# HMC5883Shield.net
KiCad netlist of a schematic drawn in EAGLE
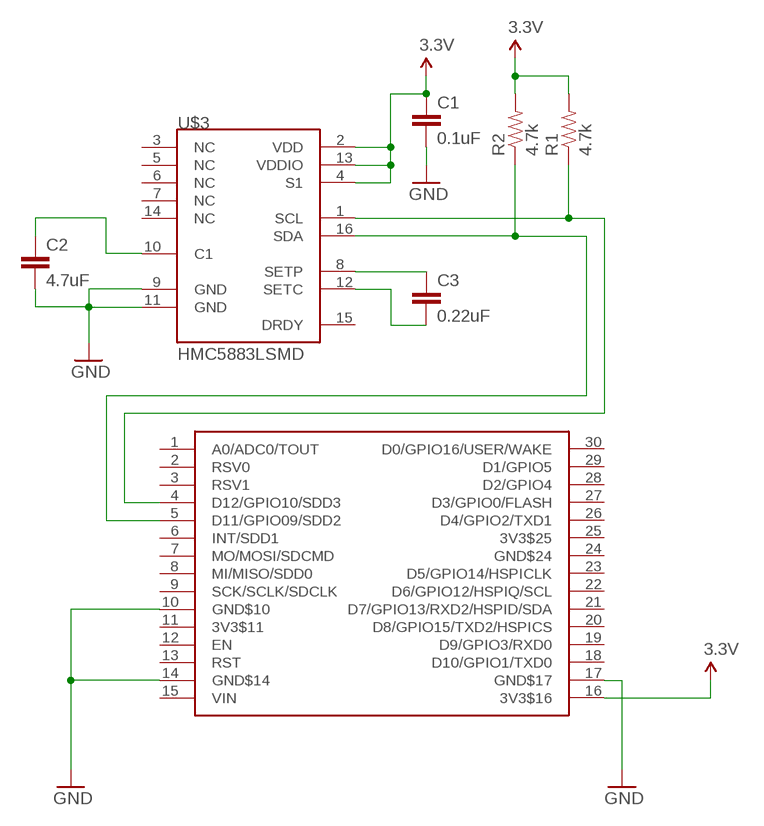
[diagram p0: schematic, sheet 1]

(export (version "E")
  (design (tool "Eeschema 10.0.6"))
  (components
    (comp (ref "C1")
      (value "0.1uF")
      (footprint "eagle-import:0402-CAP")
      (libsource (lib "eagle-import") (part "CAP0402-CAP"))
    )
    (comp (ref "C2")
      (value "4.7uF")
      (footprint "eagle-import:0402-CAP")
      (libsource (lib "eagle-import") (part "CAP0402-CAP"))
    )
    (comp (ref "C3")
      (value "0.22uF")
      (footprint "eagle-import:0402-CAP")
      (libsource (lib "eagle-import") (part "CAP0402-CAP"))
    )
    (comp (ref "R1")
      (value "4.7k")
      (footprint "eagle-import:0402-RES")
      (libsource (lib "eagle-import") (part "RESISTOR0402-RES"))
    )
    (comp (ref "R2")
      (value "4.7k")
      (footprint "eagle-import:0402-RES")
      (libsource (lib "eagle-import") (part "RESISTOR0402-RES"))
    )
    (comp (ref "U$1")
      (value "NERDSHIELD")
      (footprint "eagle-import:NERDUINO_STACK")
      (libsource (lib "eagle-import") (part "NERDSHIELD"))
    )
    (comp (ref "U$3")
      (value "HMC5883LSMD")
      (footprint "eagle-import:16LPCC")
      (libsource (lib "eagle-import") (part "HMC5883LSMD"))
    )
  )
  (nets
    (net (code "1") (name "3.3V") (class "Default")
      (node (ref "C1") (pin "1") (pinfunction "1_1") (pintype "passive"))
      (node (ref "R1") (pin "2") (pinfunction "2_2") (pintype "passive"))
      (node (ref "R2") (pin "2") (pinfunction "2_2") (pintype "passive"))
      (node (ref "U$1") (pin "16") (pinfunction "3V3$16_16") (pintype "bidirectional"))
      (node (ref "U$3") (pin "13") (pinfunction "VDDIO_13") (pintype "bidirectional"))
      (node (ref "U$3") (pin "2") (pinfunction "VDD_2") (pintype "bidirectional"))
      (node (ref "U$3") (pin "4") (pinfunction "S1_4") (pintype "bidirectional"))
    )
    (net (code "2") (name "GND") (class "Default")
      (node (ref "C1") (pin "2") (pinfunction "2_2") (pintype "passive"))
      (node (ref "C2") (pin "2") (pinfunction "2_2") (pintype "passive"))
      (node (ref "U$1") (pin "10") (pinfunction "GND$10_10") (pintype "bidirectional"))
      (node (ref "U$1") (pin "14") (pinfunction "GND$14_14") (pintype "bidirectional"))
      (node (ref "U$1") (pin "17") (pinfunction "GND$17_17") (pintype "bidirectional"))
      (node (ref "U$3") (pin "11") (pinfunction "GND_11") (pintype "bidirectional"))
      (node (ref "U$3") (pin "9") (pinfunction "GND_9") (pintype "bidirectional"))
    )
    (net (code "3") (name "Net-(U$1-D11{slash}GPIO09{slash}SDD2)") (class "Default")
      (node (ref "R2") (pin "1") (pinfunction "1_1") (pintype "passive"))
      (node (ref "U$1") (pin "5") (pinfunction "D11/GPIO09/SDD2_5") (pintype "bidirectional"))
      (node (ref "U$3") (pin "16") (pinfunction "SDA_16") (pintype "bidirectional"))
    )
    (net (code "4") (name "Net-(U$1-D12{slash}GPIO10{slash}SDD3)") (class "Default")
      (node (ref "R1") (pin "1") (pinfunction "1_1") (pintype "passive"))
      (node (ref "U$1") (pin "4") (pinfunction "D12/GPIO10/SDD3_4") (pintype "bidirectional"))
      (node (ref "U$3") (pin "1") (pinfunction "SCL_1") (pintype "bidirectional"))
    )
    (net (code "5") (name "Net-(U$3-C1)") (class "Default")
      (node (ref "C2") (pin "1") (pinfunction "1_1") (pintype "passive"))
      (node (ref "U$3") (pin "10") (pinfunction "C1_10") (pintype "bidirectional"))
    )
    (net (code "6") (name "Net-(U$3-SETC)") (class "Default")
      (node (ref "C3") (pin "2") (pinfunction "2_2") (pintype "passive"))
      (node (ref "U$3") (pin "12") (pinfunction "SETC_12") (pintype "bidirectional"))
    )
    (net (code "7") (name "Net-(U$3-SETP)") (class "Default")
      (node (ref "C3") (pin "1") (pinfunction "1_1") (pintype "passive"))
      (node (ref "U$3") (pin "8") (pinfunction "SETP_8") (pintype "bidirectional"))
    )
    (net (code "8") (name "unconnected-(U$1-3V3$11-Pad11)") (class "Default")
      (node (ref "U$1") (pin "11") (pinfunction "3V3$11_11") (pintype "bidirectional"))
    )
    (net (code "9") (name "unconnected-(U$1-3V3$25-Pad25)") (class "Default")
      (node (ref "U$1") (pin "25") (pinfunction "3V3$25_25") (pintype "bidirectional"))
    )
    (net (code "10") (name "unconnected-(U$1-A0{slash}ADC0{slash}TOUT-Pad1)") (class "Default")
      (node (ref "U$1") (pin "1") (pinfunction "A0/ADC0/TOUT_1") (pintype "bidirectional"))
    )
    (net (code "11") (name "unconnected-(U$1-D0{slash}GPIO16{slash}USER{slash}WAKE-Pad30)") (class "Default")
      (node (ref "U$1") (pin "30") (pinfunction "D0/GPIO16/USER/WAKE_30") (pintype "bidirectional"))
    )
    (net (code "12") (name "unconnected-(U$1-D1{slash}GPIO5-Pad29)") (class "Default")
      (node (ref "U$1") (pin "29") (pinfunction "D1/GPIO5_29") (pintype "bidirectional"))
    )
    (net (code "13") (name "unconnected-(U$1-D2{slash}GPIO4-Pad28)") (class "Default")
      (node (ref "U$1") (pin "28") (pinfunction "D2/GPIO4_28") (pintype "bidirectional"))
    )
    (net (code "14") (name "unconnected-(U$1-D3{slash}GPIO0{slash}FLASH-Pad27)") (class "Default")
      (node (ref "U$1") (pin "27") (pinfunction "D3/GPIO0/FLASH_27") (pintype "bidirectional"))
    )
    (net (code "15") (name "unconnected-(U$1-D4{slash}GPIO2{slash}TXD1-Pad26)") (class "Default")
      (node (ref "U$1") (pin "26") (pinfunction "D4/GPIO2/TXD1_26") (pintype "bidirectional"))
    )
    (net (code "16") (name "unconnected-(U$1-D5{slash}GPIO14{slash}HSPICLK-Pad23)") (class "Default")
      (node (ref "U$1") (pin "23") (pinfunction "D5/GPIO14/HSPICLK_23") (pintype "bidirectional"))
    )
    (net (code "17") (name "unconnected-(U$1-D6{slash}GPIO12{slash}HSPIQ{slash}SCL-Pad22)") (class "Default")
      (node (ref "U$1") (pin "22") (pinfunction "D6/GPIO12/HSPIQ/SCL_22") (pintype "bidirectional"))
    )
    (net (code "18") (name "unconnected-(U$1-D7{slash}GPIO13{slash}RXD2{slash}HSPID{slash}SDA-Pad21)") (class "Default")
      (node (ref "U$1") (pin "21") (pinfunction "D7/GPIO13/RXD2/HSPID/SDA_21") (pintype "bidirectional"))
    )
    (net (code "19") (name "unconnected-(U$1-D8{slash}GPIO15{slash}TXD2{slash}HSPICS-Pad20)") (class "Default")
      (node (ref "U$1") (pin "20") (pinfunction "D8/GPIO15/TXD2/HSPICS_20") (pintype "bidirectional"))
    )
    (net (code "20") (name "unconnected-(U$1-D9{slash}GPIO3{slash}RXD0-Pad19)") (class "Default")
      (node (ref "U$1") (pin "19") (pinfunction "D9/GPIO3/RXD0_19") (pintype "bidirectional"))
    )
    (net (code "21") (name "unconnected-(U$1-D10{slash}GPIO1{slash}TXD0-Pad18)") (class "Default")
      (node (ref "U$1") (pin "18") (pinfunction "D10/GPIO1/TXD0_18") (pintype "bidirectional"))
    )
    (net (code "22") (name "unconnected-(U$1-EN-Pad12)") (class "Default")
      (node (ref "U$1") (pin "12") (pinfunction "EN_12") (pintype "bidirectional"))
    )
    (net (code "23") (name "unconnected-(U$1-GND$24-Pad24)") (class "Default")
      (node (ref "U$1") (pin "24") (pinfunction "GND$24_24") (pintype "bidirectional"))
    )
    (net (code "24") (name "unconnected-(U$1-INT{slash}SDD1-Pad6)") (class "Default")
      (node (ref "U$1") (pin "6") (pinfunction "INT/SDD1_6") (pintype "bidirectional"))
    )
    (net (code "25") (name "unconnected-(U$1-MI{slash}MISO{slash}SDD0-Pad8)") (class "Default")
      (node (ref "U$1") (pin "8") (pinfunction "MI/MISO/SDD0_8") (pintype "bidirectional"))
    )
    (net (code "26") (name "unconnected-(U$1-MO{slash}MOSI{slash}SDCMD-Pad7)") (class "Default")
      (node (ref "U$1") (pin "7") (pinfunction "MO/MOSI/SDCMD_7") (pintype "bidirectional"))
    )
    (net (code "27") (name "unconnected-(U$1-RST-Pad13)") (class "Default")
      (node (ref "U$1") (pin "13") (pinfunction "RST_13") (pintype "bidirectional"))
    )
    (net (code "28") (name "unconnected-(U$1-RSV0-Pad2)") (class "Default")
      (node (ref "U$1") (pin "2") (pinfunction "RSV0_2") (pintype "bidirectional"))
    )
    (net (code "29") (name "unconnected-(U$1-RSV1-Pad3)") (class "Default")
      (node (ref "U$1") (pin "3") (pinfunction "RSV1_3") (pintype "bidirectional"))
    )
    (net (code "30") (name "unconnected-(U$1-SCK{slash}SCLK{slash}SDCLK-Pad9)") (class "Default")
      (node (ref "U$1") (pin "9") (pinfunction "SCK/SCLK/SDCLK_9") (pintype "bidirectional"))
    )
    (net (code "31") (name "unconnected-(U$1-VIN-Pad15)") (class "Default")
      (node (ref "U$1") (pin "15") (pinfunction "VIN_15") (pintype "bidirectional"))
    )
    (net (code "32") (name "unconnected-(U$3-DRDY-Pad15)") (class "Default")
      (node (ref "U$3") (pin "15") (pinfunction "DRDY_15") (pintype "bidirectional"))
    )
    (net (code "33") (name "unconnected-(U$3-NC-Pad3)") (class "Default")
      (node (ref "U$3") (pin "3") (pinfunction "NC_3") (pintype "bidirectional"))
    )
    (net (code "34") (name "unconnected-(U$3-NC-Pad5)") (class "Default")
      (node (ref "U$3") (pin "5") (pinfunction "NC_5") (pintype "bidirectional"))
    )
    (net (code "35") (name "unconnected-(U$3-NC-Pad6)") (class "Default")
      (node (ref "U$3") (pin "6") (pinfunction "NC_6") (pintype "bidirectional"))
    )
    (net (code "36") (name "unconnected-(U$3-NC-Pad7)") (class "Default")
      (node (ref "U$3") (pin "7") (pinfunction "NC_7") (pintype "bidirectional"))
    )
    (net (code "37") (name "unconnected-(U$3-NC-Pad14)") (class "Default")
      (node (ref "U$3") (pin "14") (pinfunction "NC_14") (pintype "bidirectional"))
    )
  )
)
